# Charge.net
KiCad netlist of a schematic drawn in Altium Designer
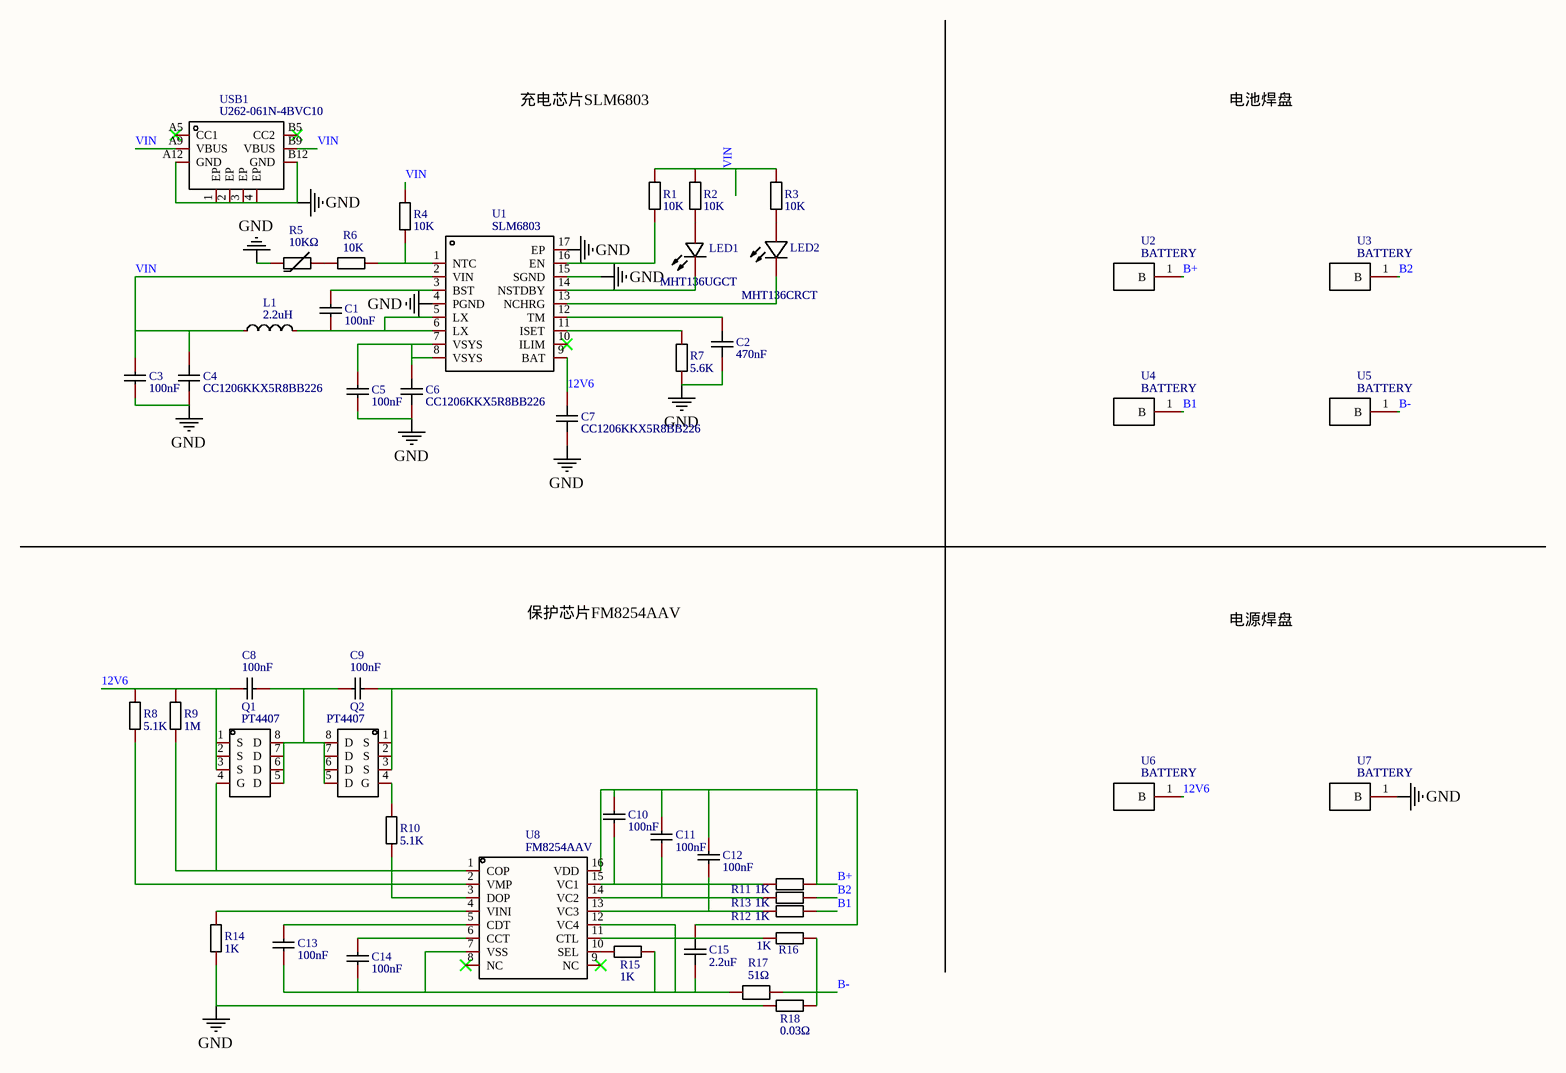
[diagram p0: Charge.schdoc]

(export (version "E")
  (design (tool "Eeschema 10.0.6"))
  (components
    (comp (ref "C1")
      (value "100nF")
      (fields
        (field (name "NAME") "100nF")
        (field (name "MANUFACTURER") "YAGEO")
        (field (name "MANUFACTURER PART") "CC0402KRX5R8BB104")
      )
      (libsource (lib "altium-import") (part "root_1_100nF_"))
    )
    (comp (ref "C2")
      (value "470nF")
      (fields
        (field (name "NAME") "470nF")
        (field (name "MANUFACTURER") "YAGEO")
        (field (name "MANUFACTURER PART") "CC0402KRX5R8BB474")
      )
      (libsource (lib "altium-import") (part "root_1_470nF_"))
    )
    (comp (ref "C3")
      (value "100nF")
      (fields
        (field (name "NAME") "100nF")
        (field (name "MANUFACTURER") "YAGEO")
        (field (name "MANUFACTURER PART") "CC0402KRX5R8BB104")
      )
      (libsource (lib "altium-import") (part "root_1_100nF_"))
    )
    (comp (ref "C4")
      (value "CC1206KKX5R8BB226")
      (fields (field (name "NAME") "CC1206KKX5R8BB226") (field (name "MANUFACTURER") "YAGEO(国巨)"))
      (libsource (lib "altium-import") (part "root_1_CC1206KKX5R8BB226_"))
    )
    (comp (ref "C5")
      (value "100nF")
      (fields
        (field (name "NAME") "100nF")
        (field (name "MANUFACTURER") "YAGEO")
        (field (name "MANUFACTURER PART") "CC0402KRX5R8BB104")
      )
      (libsource (lib "altium-import") (part "root_1_100nF_"))
    )
    (comp (ref "C6")
      (value "CC1206KKX5R8BB226")
      (fields (field (name "NAME") "CC1206KKX5R8BB226") (field (name "MANUFACTURER") "YAGEO(国巨)"))
      (libsource (lib "altium-import") (part "root_1_CC1206KKX5R8BB226_"))
    )
    (comp (ref "C7")
      (value "CC1206KKX5R8BB226")
      (fields (field (name "NAME") "CC1206KKX5R8BB226") (field (name "MANUFACTURER") "YAGEO(国巨)"))
      (libsource (lib "altium-import") (part "root_1_CC1206KKX5R8BB226_"))
    )
    (comp (ref "C8")
      (value "100nF")
      (fields
        (field (name "NAME") "100nF")
        (field (name "MANUFACTURER") "YAGEO")
        (field (name "MANUFACTURER PART") "CC0402KRX5R8BB104")
      )
      (libsource (lib "altium-import") (part "root_2_100nF_"))
    )
    (comp (ref "C9")
      (value "100nF")
      (fields
        (field (name "NAME") "100nF")
        (field (name "MANUFACTURER") "YAGEO")
        (field (name "MANUFACTURER PART") "CC0402KRX5R8BB104")
      )
      (libsource (lib "altium-import") (part "root_2_100nF_"))
    )
    (comp (ref "C10")
      (value "100nF")
      (fields
        (field (name "NAME") "100nF")
        (field (name "MANUFACTURER") "YAGEO")
        (field (name "MANUFACTURER PART") "CC0402KRX5R8BB104")
      )
      (libsource (lib "altium-import") (part "root_3_100nF_"))
    )
    (comp (ref "C11")
      (value "100nF")
      (fields
        (field (name "NAME") "100nF")
        (field (name "MANUFACTURER") "YAGEO")
        (field (name "MANUFACTURER PART") "CC0402KRX5R8BB104")
      )
      (libsource (lib "altium-import") (part "root_3_100nF_"))
    )
    (comp (ref "C12")
      (value "100nF")
      (fields
        (field (name "NAME") "100nF")
        (field (name "MANUFACTURER") "YAGEO")
        (field (name "MANUFACTURER PART") "CC0402KRX5R8BB104")
      )
      (libsource (lib "altium-import") (part "root_3_100nF_"))
    )
    (comp (ref "C13")
      (value "100nF")
      (fields
        (field (name "NAME") "100nF")
        (field (name "MANUFACTURER") "YAGEO")
        (field (name "MANUFACTURER PART") "CC0402KRX5R8BB104")
      )
      (libsource (lib "altium-import") (part "root_1_100nF_"))
    )
    (comp (ref "C14")
      (value "100nF")
      (fields
        (field (name "NAME") "100nF")
        (field (name "MANUFACTURER") "YAGEO")
        (field (name "MANUFACTURER PART") "CC0402KRX5R8BB104")
      )
      (libsource (lib "altium-import") (part "root_1_100nF_"))
    )
    (comp (ref "C15")
      (value "2.2uF")
      (fields
        (field (name "NAME") "2.2uF")
        (field (name "MANUFACTURER") "YAGEO")
        (field (name "MANUFACTURER PART") "CC0402KRX5R8BB225")
      )
      (libsource (lib "altium-import") (part "root_1_2.2uF_"))
    )
    (comp (ref "L1")
      (value "2.2uH")
      (fields
        (field (name "NAME") "2.2uH")
        (field (name "MANUFACTURER") "Sunltech Tech")
        (field (name "MANUFACTURER PART") "SLO1040H2R2MTT")
      )
      (libsource (lib "altium-import") (part "root_0_2.2uH_"))
    )
    (comp (ref "LED1")
      (value "MHT136UGCT")
      (fields (field (name "NAME") "MHT136UGCT") (field (name "MANUFACTURER") "MEIHUA"))
      (libsource (lib "altium-import") (part "root_1_MHT136UGCT_"))
    )
    (comp (ref "LED2")
      (value "MHT136CRCT")
      (fields (field (name "NAME") "MHT136CRCT") (field (name "MANUFACTURER") "MEIHUA"))
      (libsource (lib "altium-import") (part "root_1_MHT136CRCT_"))
    )
    (comp (ref "Q1")
      (value "PT4407")
      (fields (field (name "NAME") "PT4407") (field (name "MANUFACTURER") "PUOLOP"))
      (libsource (lib "") (part "root_0_PT4407__1"))
    )
    (comp (ref "Q2")
      (value "PT4407")
      (fields (field (name "NAME") "PT4407") (field (name "MANUFACTURER") "PUOLOP"))
      (libsource (lib "altium-import") (part "root_0_PT4407_"))
    )
    (comp (ref "R1")
      (value "10K")
      (fields
        (field (name "NAME") "10K")
        (field (name "MANUFACTURER") "YAGEO")
        (field (name "MANUFACTURER PART") "RC0402FR-0710KL")
      )
      (libsource (lib "altium-import") (part "root_1_10K_"))
    )
    (comp (ref "R2")
      (value "10K")
      (fields
        (field (name "NAME") "10K")
        (field (name "MANUFACTURER") "YAGEO")
        (field (name "MANUFACTURER PART") "RC0402FR-0710KL")
      )
      (libsource (lib "altium-import") (part "root_1_10K_"))
    )
    (comp (ref "R3")
      (value "10K")
      (fields
        (field (name "NAME") "10K")
        (field (name "MANUFACTURER") "YAGEO")
        (field (name "MANUFACTURER PART") "RC0402FR-0710KL")
      )
      (libsource (lib "altium-import") (part "root_1_10K_"))
    )
    (comp (ref "R4")
      (value "10K")
      (fields
        (field (name "NAME") "10K")
        (field (name "MANUFACTURER") "YAGEO")
        (field (name "MANUFACTURER PART") "RC0402FR-0710KL")
      )
      (libsource (lib "altium-import") (part "root_1_10K_"))
    )
    (comp (ref "R5")
      (value "10KΩ")
      (fields
        (field (name "NAME") "10KΩ")
        (field (name "MANUFACTURER") "Sunlord")
        (field (name "MANUFACTURER PART") "SDNT2012X103J3450HTF")
      )
      (libsource (lib "altium-import") (part "root_0_10KΩ_"))
    )
    (comp (ref "R6")
      (value "10K")
      (fields
        (field (name "NAME") "10K")
        (field (name "MANUFACTURER") "YAGEO")
        (field (name "MANUFACTURER PART") "RC0402FR-0710KL")
      )
      (libsource (lib "altium-import") (part "root_2_10K_"))
    )
    (comp (ref "R7")
      (value "5.6K")
      (fields
        (field (name "NAME") "5.6K")
        (field (name "MANUFACTURER") "YAGEO")
        (field (name "MANUFACTURER PART") "RC0402FR-075K6L")
      )
      (libsource (lib "altium-import") (part "root_1_5.6K_"))
    )
    (comp (ref "R8")
      (value "5.1K")
      (fields
        (field (name "NAME") "5.1K")
        (field (name "MANUFACTURER") "YAGEO")
        (field (name "MANUFACTURER PART") "RC0402FR-075K1L")
      )
      (libsource (lib "altium-import") (part "root_1_5.1K_"))
    )
    (comp (ref "R9")
      (value "1M")
      (fields
        (field (name "NAME") "1M")
        (field (name "MANUFACTURER") "YAGEO")
        (field (name "MANUFACTURER PART") "RC0402FR-071ML")
      )
      (libsource (lib "altium-import") (part "root_1_1M_"))
    )
    (comp (ref "R10")
      (value "5.1K")
      (fields
        (field (name "NAME") "5.1K")
        (field (name "MANUFACTURER") "YAGEO")
        (field (name "MANUFACTURER PART") "RC0402FR-075K1L")
      )
      (libsource (lib "altium-import") (part "root_1_5.1K_"))
    )
    (comp (ref "R11")
      (value "1K")
      (fields
        (field (name "NAME") "1K")
        (field (name "MANUFACTURER") "YAGEO")
        (field (name "MANUFACTURER PART") "AC0402FR-071KL")
      )
      (libsource (lib "altium-import") (part "root_2_1K_"))
    )
    (comp (ref "R12")
      (value "1K")
      (fields
        (field (name "NAME") "1K")
        (field (name "MANUFACTURER") "YAGEO")
        (field (name "MANUFACTURER PART") "AC0402FR-071KL")
      )
      (libsource (lib "altium-import") (part "root_2_1K_"))
    )
    (comp (ref "R13")
      (value "1K")
      (fields
        (field (name "NAME") "1K")
        (field (name "MANUFACTURER") "YAGEO")
        (field (name "MANUFACTURER PART") "AC0402FR-071KL")
      )
      (libsource (lib "altium-import") (part "root_2_1K_"))
    )
    (comp (ref "R14")
      (value "1K")
      (fields
        (field (name "NAME") "1K")
        (field (name "MANUFACTURER") "YAGEO")
        (field (name "MANUFACTURER PART") "AC0402FR-071KL")
      )
      (libsource (lib "altium-import") (part "root_1_1K_"))
    )
    (comp (ref "R15")
      (value "1K")
      (fields
        (field (name "NAME") "1K")
        (field (name "MANUFACTURER") "YAGEO")
        (field (name "MANUFACTURER PART") "AC0402FR-071KL")
      )
      (libsource (lib "altium-import") (part "root_2_1K_"))
    )
    (comp (ref "R16")
      (value "1K")
      (fields
        (field (name "NAME") "1K")
        (field (name "MANUFACTURER") "YAGEO")
        (field (name "MANUFACTURER PART") "AC0402FR-071KL")
      )
      (libsource (lib "altium-import") (part "root_2_1K_"))
    )
    (comp (ref "R17")
      (value "51Ω")
      (fields
        (field (name "NAME") "51Ω")
        (field (name "MANUFACTURER") "ROHM(罗姆)")
        (field (name "MANUFACTURER PART") "ESR03EZPF51R0")
      )
      (libsource (lib "altium-import") (part "root_0_51Ω_"))
    )
    (comp (ref "R18")
      (value "0.03Ω")
      (fields
        (field (name "NAME") "0.03Ω")
        (field (name "MANUFACTURER") "PSA")
        (field (name "MANUFACTURER PART") "FMF25FPJR030-LHL")
      )
      (libsource (lib "altium-import") (part "root_0_0.03Ω_"))
    )
    (comp (ref "U1")
      (value "SLM6803")
      (fields (field (name "NAME") "SLM6803") (field (name "MANUFACTURER") "SOLA-IC"))
      (libsource (lib "altium-import") (part "root_0_SLM6803_"))
    )
    (comp (ref "U2")
      (value "BATTERY")
      (fields (field (name "NAME") "BATTERY"))
      (libsource (lib "altium-import") (part "root_0_BATTERY_"))
    )
    (comp (ref "U3")
      (value "BATTERY")
      (fields (field (name "NAME") "BATTERY"))
      (libsource (lib "altium-import") (part "root_0_BATTERY_"))
    )
    (comp (ref "U4")
      (value "BATTERY")
      (fields (field (name "NAME") "BATTERY"))
      (libsource (lib "altium-import") (part "root_0_BATTERY_"))
    )
    (comp (ref "U5")
      (value "BATTERY")
      (fields (field (name "NAME") "BATTERY"))
      (libsource (lib "altium-import") (part "root_0_BATTERY_"))
    )
    (comp (ref "U6")
      (value "BATTERY")
      (fields (field (name "NAME") "BATTERY"))
      (libsource (lib "altium-import") (part "root_0_BATTERY_"))
    )
    (comp (ref "U7")
      (value "BATTERY")
      (fields (field (name "NAME") "BATTERY"))
      (libsource (lib "altium-import") (part "root_0_BATTERY_"))
    )
    (comp (ref "U8")
      (value "FM8254AAV")
      (fields (field (name "NAME") "FM8254AAV") (field (name "MANUFACTURER") "Shenzhen Fuman Elec"))
      (libsource (lib "altium-import") (part "root_0_FM8254AAV_"))
    )
    (comp (ref "USB1")
      (value "U262-061N-4BVC10")
      (fields (field (name "NAME") "U262-061N-4BVC10") (field (name "MANUFACTURER") "XKB Connectivity"))
      (libsource (lib "altium-import") (part "root_0_U262-061N-4BVC10_"))
    )
  )
  (nets
    (net (code "1") (name "/12V6") (class "Default")
      (node (ref "C7") (pin "2") (pinfunction "2_2") (pintype "passive"))
      (node (ref "C8") (pin "2") (pinfunction "2_2") (pintype "passive"))
      (node (ref "Q1") (pin "1") (pinfunction "S_1") (pintype "passive"))
      (node (ref "Q1") (pin "2") (pinfunction "S_2") (pintype "passive"))
      (node (ref "Q1") (pin "3") (pinfunction "S_3") (pintype "passive"))
      (node (ref "R8") (pin "2") (pinfunction "2_2") (pintype "passive"))
      (node (ref "R9") (pin "2") (pinfunction "2_2") (pintype "passive"))
      (node (ref "U1") (pin "9") (pinfunction "BAT_9") (pintype "passive"))
      (node (ref "U6") (pin "1") (pinfunction "B_1") (pintype "passive"))
    )
    (net (code "2") (name "/B+") (class "Default")
      (node (ref "C10") (pin "1") (pinfunction "1_1") (pintype "passive"))
      (node (ref "C11") (pin "1") (pinfunction "1_1") (pintype "passive"))
      (node (ref "C12") (pin "1") (pinfunction "1_1") (pintype "passive"))
      (node (ref "C15") (pin "2") (pinfunction "2_2") (pintype "passive"))
      (node (ref "C9") (pin "1") (pinfunction "1_1") (pintype "passive"))
      (node (ref "Q2") (pin "1") (pinfunction "S_1") (pintype "passive"))
      (node (ref "Q2") (pin "2") (pinfunction "S_2") (pintype "passive"))
      (node (ref "Q2") (pin "3") (pinfunction "S_3") (pintype "passive"))
      (node (ref "R11") (pin "1") (pinfunction "1_1") (pintype "passive"))
      (node (ref "U2") (pin "1") (pinfunction "B_1") (pintype "passive"))
      (node (ref "U8") (pin "16") (pinfunction "VDD_16") (pintype "passive"))
    )
    (net (code "3") (name "/B-") (class "Default")
      (node (ref "R16") (pin "1") (pinfunction "1_1") (pintype "passive"))
      (node (ref "R17") (pin "2") (pinfunction "2_2") (pintype "passive"))
      (node (ref "R18") (pin "2") (pinfunction "2_2") (pintype "passive"))
      (node (ref "U5") (pin "1") (pinfunction "B_1") (pintype "passive"))
    )
    (net (code "4") (name "/B1") (class "Default")
      (node (ref "R12") (pin "1") (pinfunction "1_1") (pintype "passive"))
      (node (ref "U4") (pin "1") (pinfunction "B_1") (pintype "passive"))
    )
    (net (code "5") (name "/B2") (class "Default")
      (node (ref "R13") (pin "1") (pinfunction "1_1") (pintype "passive"))
      (node (ref "U3") (pin "1") (pinfunction "B_1") (pintype "passive"))
    )
    (net (code "6") (name "/VIN") (class "Default")
      (node (ref "C3") (pin "2") (pinfunction "2_2") (pintype "passive"))
      (node (ref "C4") (pin "2") (pinfunction "2_2") (pintype "passive"))
      (node (ref "L1") (pin "1") (pinfunction "1_1") (pintype "passive"))
      (node (ref "R1") (pin "2") (pinfunction "2_2") (pintype "passive"))
      (node (ref "R2") (pin "2") (pinfunction "2_2") (pintype "passive"))
      (node (ref "R3") (pin "2") (pinfunction "2_2") (pintype "passive"))
      (node (ref "R4") (pin "2") (pinfunction "2_2") (pintype "passive"))
      (node (ref "U1") (pin "2") (pinfunction "VIN_2") (pintype "passive"))
      (node (ref "USB1") (pin "A9") (pinfunction "VBUS_A9") (pintype "passive"))
      (node (ref "USB1") (pin "B9") (pinfunction "VBUS_B9") (pintype "passive"))
    )
    (net (code "7") (name "GND") (class "Default")
      (node (ref "C2") (pin "1") (pinfunction "1_1") (pintype "passive"))
      (node (ref "C3") (pin "1") (pinfunction "1_1") (pintype "passive"))
      (node (ref "C4") (pin "1") (pinfunction "1_1") (pintype "passive"))
      (node (ref "C5") (pin "1") (pinfunction "1_1") (pintype "passive"))
      (node (ref "C6") (pin "1") (pinfunction "1_1") (pintype "passive"))
      (node (ref "C7") (pin "1") (pinfunction "1_1") (pintype "passive"))
      (node (ref "R14") (pin "1") (pinfunction "1_1") (pintype "passive"))
      (node (ref "R18") (pin "1") (pinfunction "1_1") (pintype "passive"))
      (node (ref "R5") (pin "1") (pinfunction "1_1") (pintype "passive"))
      (node (ref "R7") (pin "1") (pinfunction "1_1") (pintype "passive"))
      (node (ref "U1") (pin "15") (pinfunction "SGND_15") (pintype "passive"))
      (node (ref "U1") (pin "17") (pinfunction "EP_17") (pintype "passive"))
      (node (ref "U1") (pin "4") (pinfunction "PGND_4") (pintype "passive"))
      (node (ref "U7") (pin "1") (pinfunction "B_1") (pintype "passive"))
      (node (ref "USB1") (pin "1") (pinfunction "EP_1") (pintype "passive"))
      (node (ref "USB1") (pin "2") (pinfunction "EP_2") (pintype "passive"))
      (node (ref "USB1") (pin "3") (pinfunction "EP_3") (pintype "passive"))
      (node (ref "USB1") (pin "4") (pinfunction "EP_4") (pintype "passive"))
      (node (ref "USB1") (pin "A12") (pinfunction "GND_A12") (pintype "passive"))
      (node (ref "USB1") (pin "B12") (pinfunction "GND_B12") (pintype "passive"))
    )
    (net (code "8") (name "Net-(C1-Pad1)") (class "Default")
      (node (ref "C1") (pin "1") (pinfunction "1_1") (pintype "passive"))
      (node (ref "L1") (pin "2") (pinfunction "2_2") (pintype "passive"))
      (node (ref "U1") (pin "5") (pinfunction "LX_5") (pintype "passive"))
      (node (ref "U1") (pin "6") (pinfunction "LX_6") (pintype "passive"))
    )
    (net (code "9") (name "Net-(C5-Pad2)") (class "Default")
      (node (ref "C5") (pin "2") (pinfunction "2_2") (pintype "passive"))
      (node (ref "C6") (pin "2") (pinfunction "2_2") (pintype "passive"))
      (node (ref "U1") (pin "7") (pinfunction "VSYS_7") (pintype "passive"))
      (node (ref "U1") (pin "8") (pinfunction "VSYS_8") (pintype "passive"))
    )
    (net (code "10") (name "Net-(C8-Pad1)") (class "Default")
      (node (ref "C8") (pin "1") (pinfunction "1_1") (pintype "passive"))
      (node (ref "C9") (pin "2") (pinfunction "2_2") (pintype "passive"))
      (node (ref "Q1") (pin "5") (pinfunction "D_5") (pintype "passive"))
      (node (ref "Q1") (pin "6") (pinfunction "D_6") (pintype "passive"))
      (node (ref "Q1") (pin "7") (pinfunction "D_7") (pintype "passive"))
      (node (ref "Q1") (pin "8") (pinfunction "D_8") (pintype "passive"))
      (node (ref "Q2") (pin "5") (pinfunction "D_5") (pintype "passive"))
      (node (ref "Q2") (pin "6") (pinfunction "D_6") (pintype "passive"))
      (node (ref "Q2") (pin "7") (pinfunction "D_7") (pintype "passive"))
      (node (ref "Q2") (pin "8") (pinfunction "D_8") (pintype "passive"))
    )
    (net (code "11") (name "Net-(LED1-+)") (class "Default")
      (node (ref "LED1") (pin "2") (pinfunction "+_2") (pintype "passive"))
      (node (ref "R2") (pin "1") (pinfunction "1_1") (pintype "passive"))
    )
    (net (code "12") (name "Net-(LED1--)") (class "Default")
      (node (ref "LED1") (pin "1") (pinfunction "-_1") (pintype "passive"))
      (node (ref "U1") (pin "14") (pinfunction "NSTDBY_14") (pintype "passive"))
    )
    (net (code "13") (name "Net-(LED2-A)") (class "Default")
      (node (ref "LED2") (pin "2") (pinfunction "A_2") (pintype "passive"))
      (node (ref "R3") (pin "1") (pinfunction "1_1") (pintype "passive"))
    )
    (net (code "14") (name "Net-(LED2-K)") (class "Default")
      (node (ref "LED2") (pin "1") (pinfunction "K_1") (pintype "passive"))
      (node (ref "U1") (pin "13") (pinfunction "NCHRG_13") (pintype "passive"))
    )
    (net (code "15") (name "Net-(Q1-G)") (class "Default")
      (node (ref "Q1") (pin "4") (pinfunction "G_4") (pintype "passive"))
      (node (ref "R9") (pin "1") (pinfunction "1_1") (pintype "passive"))
      (node (ref "U8") (pin "1") (pinfunction "COP_1") (pintype "passive"))
    )
    (net (code "16") (name "Net-(Q2-G)") (class "Default")
      (node (ref "Q2") (pin "4") (pinfunction "G_4") (pintype "passive"))
      (node (ref "R10") (pin "2") (pinfunction "2_2") (pintype "passive"))
    )
    (net (code "17") (name "Net-(R5-Pad2)") (class "Default")
      (node (ref "R5") (pin "2") (pinfunction "2_2") (pintype "passive"))
      (node (ref "R6") (pin "2") (pinfunction "2_2") (pintype "passive"))
    )
    (net (code "18") (name "Net-(U1-BST)") (class "Default")
      (node (ref "C1") (pin "2") (pinfunction "2_2") (pintype "passive"))
      (node (ref "U1") (pin "3") (pinfunction "BST_3") (pintype "passive"))
    )
    (net (code "19") (name "Net-(U1-EN)") (class "Default")
      (node (ref "R1") (pin "1") (pinfunction "1_1") (pintype "passive"))
      (node (ref "U1") (pin "16") (pinfunction "EN_16") (pintype "passive"))
    )
    (net (code "20") (name "Net-(U1-ISET)") (class "Default")
      (node (ref "R7") (pin "2") (pinfunction "2_2") (pintype "passive"))
      (node (ref "U1") (pin "11") (pinfunction "ISET_11") (pintype "passive"))
    )
    (net (code "21") (name "Net-(U1-NTC)") (class "Default")
      (node (ref "R4") (pin "1") (pinfunction "1_1") (pintype "passive"))
      (node (ref "R6") (pin "1") (pinfunction "1_1") (pintype "passive"))
      (node (ref "U1") (pin "1") (pinfunction "NTC_1") (pintype "passive"))
    )
    (net (code "22") (name "Net-(U1-TM)") (class "Default")
      (node (ref "C2") (pin "2") (pinfunction "2_2") (pintype "passive"))
      (node (ref "U1") (pin "12") (pinfunction "TM_12") (pintype "passive"))
    )
    (net (code "23") (name "Net-(U8-CCT)") (class "Default")
      (node (ref "C14") (pin "2") (pinfunction "2_2") (pintype "passive"))
      (node (ref "U8") (pin "6") (pinfunction "CCT_6") (pintype "passive"))
    )
    (net (code "24") (name "Net-(U8-CDT)") (class "Default")
      (node (ref "C13") (pin "2") (pinfunction "2_2") (pintype "passive"))
      (node (ref "U8") (pin "5") (pinfunction "CDT_5") (pintype "passive"))
    )
    (net (code "25") (name "Net-(U8-CTL)") (class "Default")
      (node (ref "R16") (pin "2") (pinfunction "2_2") (pintype "passive"))
      (node (ref "U8") (pin "11") (pinfunction "CTL_11") (pintype "passive"))
    )
    (net (code "26") (name "Net-(U8-DOP)") (class "Default")
      (node (ref "R10") (pin "1") (pinfunction "1_1") (pintype "passive"))
      (node (ref "U8") (pin "3") (pinfunction "DOP_3") (pintype "passive"))
    )
    (net (code "27") (name "Net-(U8-SEL)") (class "Default")
      (node (ref "R15") (pin "2") (pinfunction "2_2") (pintype "passive"))
      (node (ref "U8") (pin "10") (pinfunction "SEL_10") (pintype "passive"))
    )
    (net (code "28") (name "Net-(U8-VC1)") (class "Default")
      (node (ref "C10") (pin "2") (pinfunction "2_2") (pintype "passive"))
      (node (ref "R11") (pin "2") (pinfunction "2_2") (pintype "passive"))
      (node (ref "U8") (pin "15") (pinfunction "VC1_15") (pintype "passive"))
    )
    (net (code "29") (name "Net-(U8-VC2)") (class "Default")
      (node (ref "C11") (pin "2") (pinfunction "2_2") (pintype "passive"))
      (node (ref "R13") (pin "2") (pinfunction "2_2") (pintype "passive"))
      (node (ref "U8") (pin "14") (pinfunction "VC2_14") (pintype "passive"))
    )
    (net (code "30") (name "Net-(U8-VC3)") (class "Default")
      (node (ref "C12") (pin "2") (pinfunction "2_2") (pintype "passive"))
      (node (ref "R12") (pin "2") (pinfunction "2_2") (pintype "passive"))
      (node (ref "U8") (pin "13") (pinfunction "VC3_13") (pintype "passive"))
    )
    (net (code "31") (name "Net-(U8-VC4)") (class "Default")
      (node (ref "C13") (pin "1") (pinfunction "1_1") (pintype "passive"))
      (node (ref "C14") (pin "1") (pinfunction "1_1") (pintype "passive"))
      (node (ref "C15") (pin "1") (pinfunction "1_1") (pintype "passive"))
      (node (ref "R15") (pin "1") (pinfunction "1_1") (pintype "passive"))
      (node (ref "R17") (pin "1") (pinfunction "1_1") (pintype "passive"))
      (node (ref "U8") (pin "12") (pinfunction "VC4_12") (pintype "passive"))
      (node (ref "U8") (pin "7") (pinfunction "VSS_7") (pintype "passive"))
    )
    (net (code "32") (name "Net-(U8-VINI)") (class "Default")
      (node (ref "R14") (pin "2") (pinfunction "2_2") (pintype "passive"))
      (node (ref "U8") (pin "4") (pinfunction "VINI_4") (pintype "passive"))
    )
    (net (code "33") (name "Net-(U8-VMP)") (class "Default")
      (node (ref "R8") (pin "1") (pinfunction "1_1") (pintype "passive"))
      (node (ref "U8") (pin "2") (pinfunction "VMP_2") (pintype "passive"))
    )
    (net (code "34") (name "unconnected-(U1-ILIM-Pad10)") (class "Default")
      (node (ref "U1") (pin "10") (pinfunction "ILIM_10") (pintype "passive+no_connect"))
    )
    (net (code "35") (name "unconnected-(U8-NC-Pad8)") (class "Default")
      (node (ref "U8") (pin "8") (pinfunction "NC_8") (pintype "passive+no_connect"))
    )
    (net (code "36") (name "unconnected-(U8-NC-Pad9)") (class "Default")
      (node (ref "U8") (pin "9") (pinfunction "NC_9") (pintype "passive+no_connect"))
    )
    (net (code "37") (name "unconnected-(USB1-CC1-PadA5)") (class "Default")
      (node (ref "USB1") (pin "A5") (pinfunction "CC1_A5") (pintype "passive+no_connect"))
    )
    (net (code "38") (name "unconnected-(USB1-CC2-PadB5)") (class "Default")
      (node (ref "USB1") (pin "B5") (pinfunction "CC2_B5") (pintype "passive+no_connect"))
    )
  )
)
